# placa_sensores.net
KiCad netlist of a schematic drawn in EAGLE
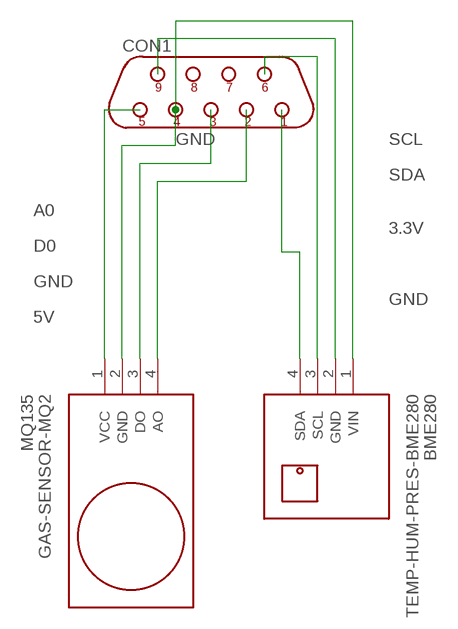
[diagram p0: schematic, sheet 1]

(export (version "E")
  (design (tool "Eeschema 10.0.6"))
  (components
    (comp (ref "BME280")
      (value "TEMP-HUM-PRES-BME280")
      (footprint "eagle-import:TEMP-HUM-PRES-BME280")
      (libsource (lib "eagle-import") (part "TEMP-HUM-PRES-BME280"))
    )
    (comp (ref "CON1")
      (value "DB9F")
      (footprint "eagle-import:D-09F")
      (libsource (lib "eagle-import") (part "DB9F"))
    )
    (comp (ref "MQ135")
      (value "GAS-SENSOR-MQ2")
      (footprint "eagle-import:GAS-SENSOR-MQ2")
      (libsource (lib "eagle-import") (part "GAS-SENSOR-MQ2"))
    )
  )
  (nets
    (net (code "1") (name "/3.3V") (class "Default")
      (node (ref "BME280") (pin "2") (pinfunction "GND_2") (pintype "power_in"))
      (node (ref "CON1") (pin "9") (pinfunction "9_9") (pintype "passive"))
    )
    (net (code "2") (name "/5V") (class "Default")
      (node (ref "CON1") (pin "5") (pinfunction "5_5") (pintype "passive"))
      (node (ref "MQ135") (pin "1") (pinfunction "VCC_1") (pintype "power_in"))
    )
    (net (code "3") (name "/A0") (class "Default")
      (node (ref "CON1") (pin "2") (pinfunction "2_2") (pintype "passive"))
      (node (ref "MQ135") (pin "4") (pinfunction "AO_4") (pintype "output"))
    )
    (net (code "4") (name "/D0") (class "Default")
      (node (ref "CON1") (pin "3") (pinfunction "3_3") (pintype "passive"))
      (node (ref "MQ135") (pin "3") (pinfunction "DO_3") (pintype "output"))
    )
    (net (code "5") (name "/GND") (class "Default")
      (node (ref "BME280") (pin "1") (pinfunction "VIN_1") (pintype "power_in"))
      (node (ref "CON1") (pin "4") (pinfunction "4_4") (pintype "passive"))
      (node (ref "MQ135") (pin "2") (pinfunction "GND_2") (pintype "power_in"))
    )
    (net (code "6") (name "/SCL") (class "Default")
      (node (ref "BME280") (pin "4") (pinfunction "SDA_4") (pintype "bidirectional"))
      (node (ref "CON1") (pin "1") (pinfunction "1_1") (pintype "passive"))
    )
    (net (code "7") (name "/SDA") (class "Default")
      (node (ref "BME280") (pin "3") (pinfunction "SCL_3") (pintype "bidirectional"))
      (node (ref "CON1") (pin "6") (pinfunction "6_6") (pintype "passive"))
    )
    (net (code "8") (name "unconnected-(CON1-Pad7)") (class "Default")
      (node (ref "CON1") (pin "7") (pinfunction "7_7") (pintype "passive"))
    )
    (net (code "9") (name "unconnected-(CON1-Pad8)") (class "Default")
      (node (ref "CON1") (pin "8") (pinfunction "8_8") (pintype "passive"))
    )
  )
)
